# 12-LCD__BIT3251.net
KiCad netlist of a schematic drawn in Altium Designer
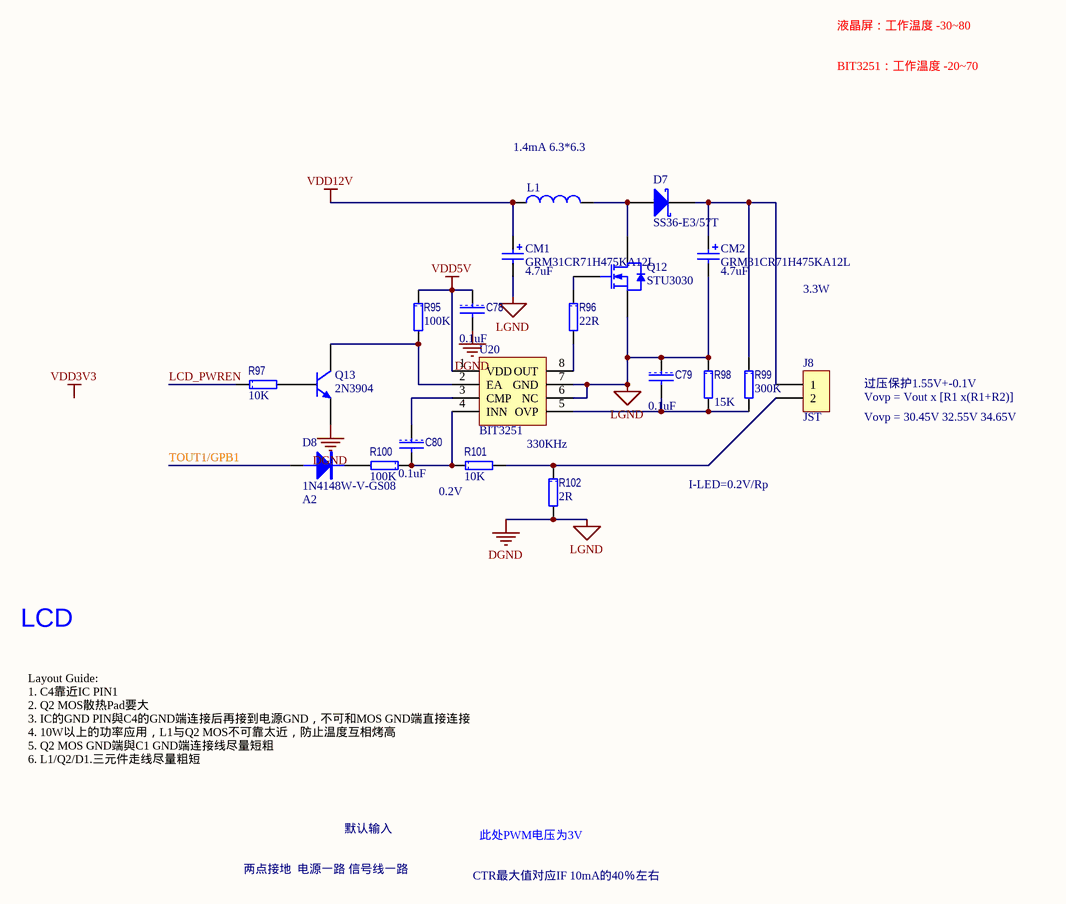
[diagram p0: 12-LCD背光驱动_BIT3251.SchDoc]

(export (version "E")
  (design (tool "Eeschema 10.0.6"))
  (components
    (comp (ref "C78")
      (value "0.1uF")
      (footprint "1608[0603]C")
      (description "多层陶瓷电容器MLCC - SMD/SMT 0603 0.1uF 50volts X7R 10%")
      (fields (field (name "MANUFACTURER") "TDK") (field (name "MANUFACTURER PART NUMBER") "C1608X7R1H104K"))
      (libsource (lib "*") (part "CAP"))
    )
    (comp (ref "C79")
      (value "0.1uF")
      (footprint "1608[0603]C")
      (description "多层陶瓷电容器MLCC - SMD/SMT 0603 0.1uF 50volts X7R 10%")
      (fields (field (name "MANUFACTURER") "TDK") (field (name "MANUFACTURER PART NUMBER") "C1608X7R1H104K"))
      (libsource (lib "*") (part "CAP"))
    )
    (comp (ref "C80")
      (value "0.1uF")
      (footprint "1608[0603]C")
      (description "多层陶瓷电容器MLCC - SMD/SMT 0603 0.1uF 50volts X7R 10%")
      (fields (field (name "MANUFACTURER") "TDK") (field (name "MANUFACTURER PART NUMBER") "C1608X7R1H104K"))
      (libsource (lib "*") (part "CAP"))
    )
    (comp (ref "CM1")
      (value "GRM31CR71H475KA12L")
      (footprint "3216[1206]C")
      (description "多层陶瓷电容器MLCC - SMD/SMT 4.7uF 50Volts 10%")
      (fields (field (name "MANUFACTURER") "Murata Electronics") (field (name "ALTIUM_VALUE") "4.7uF"))
      (libsource (lib "Miscellaneous Devices") (part "Cap Pol2"))
    )
    (comp (ref "CM2")
      (value "GRM31CR71H475KA12L")
      (footprint "3216[1206]C")
      (description "多层陶瓷电容器MLCC - SMD/SMT 4.7uF 50Volts 10%")
      (fields (field (name "MANUFACTURER") "Murata Electronics") (field (name "ALTIUM_VALUE") "4.7uF"))
      (libsource (lib "Miscellaneous Devices") (part "Cap Pol2"))
    )
    (comp (ref "D7")
      (value "SS36-E3/57T")
      (footprint "2440PCBV5:DO-214AB/SMC")
      (description "肖特基二极管与整流器 3.0 Amp 60 Volt")
      (fields (field (name "MANUFACTURER") "Vishay Semiconductors"))
      (libsource (lib "Miscellaneous Devices") (part "D Schottky"))
    )
    (comp (ref "D8")
      (value "1N4148W-V-GS08")
      (footprint "SOD123")
      (description "二极管 - 通用，功率，开关 100V Io/150mA")
      (fields (field (name "MANUFACTURER") "Vishay Semiconductors") (field (name "ALTIUM_VALUE") "A2"))
      (libsource (lib "IN4148") (part "1N4148W"))
    )
    (comp (ref "J8") (value "JST") (footprint "JST") (description "CON") (libsource (lib "*") (part "CON2")))
    (comp (ref "L1")
      (value "SLF6045T-220M1R1-3PF")
      (footprint "INDP5050X28N")
      (description "固定电感器 SMD Power Inductor")
      (libsource (lib "Miscellaneous Devices") (part "Inductor"))
    )
    (comp (ref "Q12")
      (value "STU3030")
      (footprint "TO-252AA_N")
      (description "NMOS")
      (fields (field (name "PUBLISHER") "Altium Limited"))
      (libsource (lib "Philips Discrete MOSFET - Power") (part "BSN254"))
    )
    (comp (ref "Q13")
      (value "2N3904")
      (footprint "SOT23_N")
      (description "NPN General Purpose Amplifier")
      (fields (field (name "PUBLISHER") "Altium Limited"))
      (libsource (lib "Miscellaneous Devices") (part "2N3904"))
    )
    (comp (ref "R95")
      (value "100K")
      (footprint "1608[0603]R")
      (description "厚膜电阻器 - SMD 1/10watt 300Kohms 1%")
      (fields
        (field (name "MANUFACTURER") "Vishay / Dale")
        (field (name "MANUFACTURER PART NUMBER") "CRCW0603300KFKEA")
      )
      (libsource (lib "300K 1%") (part "RES"))
    )
    (comp (ref "R96")
      (value "22R")
      (footprint "1608[0603]R")
      (description "厚膜电阻器 - SMD 1/10watt 22ohms 1%")
      (fields
        (field (name "MANUFACTURER") "Vishay / Dale")
        (field (name "MANUFACTURER PART NUMBER") "CRCW060322R0FKEA")
      )
      (libsource (lib "22R 1%") (part "RES"))
    )
    (comp (ref "R97")
      (value "10K")
      (footprint "1608[0603]R")
      (description "厚膜电阻器 - SMD 1/10watt 10Kohms 1%")
      (fields
        (field (name "MANUFACTURER") "Vishay / Dale")
        (field (name "MANUFACTURER PART NUMBER") "CRCW060310K0FKEA")
      )
      (libsource (lib "10K 1%") (part "RES"))
    )
    (comp (ref "R98")
      (value "15K")
      (footprint "1608[0603]R")
      (description "厚膜电阻器 - SMD 1/10watt 15Kohms 1%")
      (fields
        (field (name "MANUFACTURER") "Vishay / Dale")
        (field (name "MANUFACTURER PART NUMBER") "CRCW060315K0FKEA")
      )
      (libsource (lib "300K 1%") (part "RES"))
    )
    (comp (ref "R99")
      (value "300K")
      (footprint "1608[0603]R")
      (description "厚膜电阻器 - SMD 1/10watt 300Kohms 1%")
      (fields
        (field (name "MANUFACTURER") "Vishay / Dale")
        (field (name "MANUFACTURER PART NUMBER") "CRCW0603300KFKEA")
      )
      (libsource (lib "300K 1%") (part "RES"))
    )
    (comp (ref "R100")
      (value "100K")
      (footprint "1608[0603]R")
      (description "厚膜电阻器 - SMD 1/10watt 300Kohms 1%")
      (fields
        (field (name "MANUFACTURER") "Vishay / Dale")
        (field (name "MANUFACTURER PART NUMBER") "CRCW0603300KFKEA")
      )
      (libsource (lib "300K 1%") (part "RES"))
    )
    (comp (ref "R101")
      (value "10K")
      (footprint "1608[0603]R")
      (description "厚膜电阻器 - SMD 1/10watt 10Kohms 1%")
      (fields
        (field (name "MANUFACTURER") "Vishay / Dale")
        (field (name "MANUFACTURER PART NUMBER") "CRCW060310K0FKEA")
      )
      (libsource (lib "10K 1%") (part "RES"))
    )
    (comp (ref "R102")
      (value "2R")
      (footprint "1608[0603]R")
      (description "厚膜电阻器 - SMD 1/10watt 2ohms 1%")
      (fields
        (field (name "MANUFACTURER") "Vishay / Dale")
        (field (name "MANUFACTURER PART NUMBER") "CRCW06032R00FKEA")
      )
      (libsource (lib "2R 1%") (part "RES"))
    )
    (comp (ref "U20")
      (value "BIT3251")
      (footprint "SOIC8_N")
      (description "IC")
      (libsource (lib "*") (part "BIT3251"))
    )
  )
  (nets
    (net (code "1") (name "/LCD_PWREN") (class "Default")
      (node (ref "R97") (pin "1") (pinfunction "1_1") (pintype "passive"))
    )
    (net (code "2") (name "/TOUT1{slash}GPB1") (class "Default")
      (node (ref "D8") (pin "1") (pinfunction "A_1") (pintype "passive"))
    )
    (net (code "3") (name "DGND") (class "Default")
      (node (ref "C78") (pin "2") (pinfunction "2_2") (pintype "passive"))
      (node (ref "C79") (pin "1") (pinfunction "1_1") (pintype "passive"))
      (node (ref "CM1") (pin "2") (pinfunction "2_2") (pintype "passive"))
      (node (ref "CM2") (pin "2") (pinfunction "2_2") (pintype "passive"))
      (node (ref "Q12") (pin "3") (pinfunction "S_3") (pintype "passive"))
      (node (ref "Q13") (pin "1") (pinfunction "E_1") (pintype "passive"))
      (node (ref "R102") (pin "2") (pinfunction "2_2") (pintype "passive"))
      (node (ref "R98") (pin "1") (pinfunction "1_1") (pintype "passive"))
      (node (ref "U20") (pin "6") (pinfunction "NC_6") (pintype "passive"))
      (node (ref "U20") (pin "7") (pinfunction "GND_7") (pintype "passive"))
    )
    (net (code "4") (name "Net-(D7-A)") (class "Default")
      (node (ref "D7") (pin "1") (pinfunction "A_1") (pintype "passive"))
      (node (ref "L1") (pin "2") (pinfunction "2_2") (pintype "passive"))
      (node (ref "Q12") (pin "4") (pinfunction "D_4") (pintype "passive"))
    )
    (net (code "5") (name "Net-(D7-K)") (class "Default")
      (node (ref "CM2") (pin "1") (pinfunction "1_1") (pintype "passive"))
      (node (ref "D7") (pin "2") (pinfunction "K_2") (pintype "passive"))
      (node (ref "J8") (pin "1") (pinfunction "1_1") (pintype "passive"))
      (node (ref "R99") (pin "1") (pinfunction "1_1") (pintype "passive"))
    )
    (net (code "6") (name "Net-(D8-K)") (class "Default")
      (node (ref "D8") (pin "2") (pinfunction "K_2") (pintype "passive"))
      (node (ref "R100") (pin "2") (pinfunction "2_2") (pintype "passive"))
    )
    (net (code "7") (name "Net-(J8-Pad2)") (class "Default")
      (node (ref "J8") (pin "2") (pinfunction "2_2") (pintype "passive"))
      (node (ref "R101") (pin "2") (pinfunction "2_2") (pintype "passive"))
      (node (ref "R102") (pin "1") (pinfunction "1_1") (pintype "passive"))
    )
    (net (code "8") (name "Net-(Q12-G)") (class "Default")
      (node (ref "Q12") (pin "1") (pinfunction "G_1") (pintype "passive"))
      (node (ref "R96") (pin "1") (pinfunction "1_1") (pintype "passive"))
    )
    (net (code "9") (name "Net-(Q13-B)") (class "Default")
      (node (ref "Q13") (pin "2") (pinfunction "B_2") (pintype "passive"))
      (node (ref "R97") (pin "2") (pinfunction "2_2") (pintype "passive"))
    )
    (net (code "10") (name "Net-(Q13-C)") (class "Default")
      (node (ref "Q13") (pin "3") (pinfunction "C_3") (pintype "passive"))
      (node (ref "R95") (pin "2") (pinfunction "2_2") (pintype "passive"))
      (node (ref "U20") (pin "2") (pinfunction "EA_2") (pintype "passive"))
    )
    (net (code "11") (name "Net-(U20-CMP)") (class "Default")
      (node (ref "C80") (pin "1") (pinfunction "1_1") (pintype "passive"))
      (node (ref "U20") (pin "3") (pinfunction "CMP_3") (pintype "passive"))
    )
    (net (code "12") (name "Net-(U20-INN)") (class "Default")
      (node (ref "C80") (pin "2") (pinfunction "2_2") (pintype "passive"))
      (node (ref "R100") (pin "1") (pinfunction "1_1") (pintype "passive"))
      (node (ref "R101") (pin "1") (pinfunction "1_1") (pintype "passive"))
      (node (ref "U20") (pin "4") (pinfunction "INN_4") (pintype "passive"))
    )
    (net (code "13") (name "Net-(U20-OUT)") (class "Default")
      (node (ref "R96") (pin "2") (pinfunction "2_2") (pintype "passive"))
      (node (ref "U20") (pin "8") (pinfunction "OUT_8") (pintype "passive"))
    )
    (net (code "14") (name "Net-(U20-OVP)") (class "Default")
      (node (ref "C79") (pin "2") (pinfunction "2_2") (pintype "passive"))
      (node (ref "R98") (pin "2") (pinfunction "2_2") (pintype "passive"))
      (node (ref "R99") (pin "2") (pinfunction "2_2") (pintype "passive"))
      (node (ref "U20") (pin "5") (pinfunction "OVP_5") (pintype "passive"))
    )
    (net (code "16") (name "VDD5V") (class "Default")
      (node (ref "C78") (pin "1") (pinfunction "1_1") (pintype "passive"))
      (node (ref "R95") (pin "1") (pinfunction "1_1") (pintype "passive"))
      (node (ref "U20") (pin "1") (pinfunction "VDD_1") (pintype "passive"))
    )
    (net (code "17") (name "VDD12V") (class "Default")
      (node (ref "CM1") (pin "1") (pinfunction "1_1") (pintype "passive"))
      (node (ref "L1") (pin "1") (pinfunction "1_1") (pintype "passive"))
    )
  )
)
